# Ethernet_Adapter.net
KiCad netlist of a schematic drawn in Altium Designer
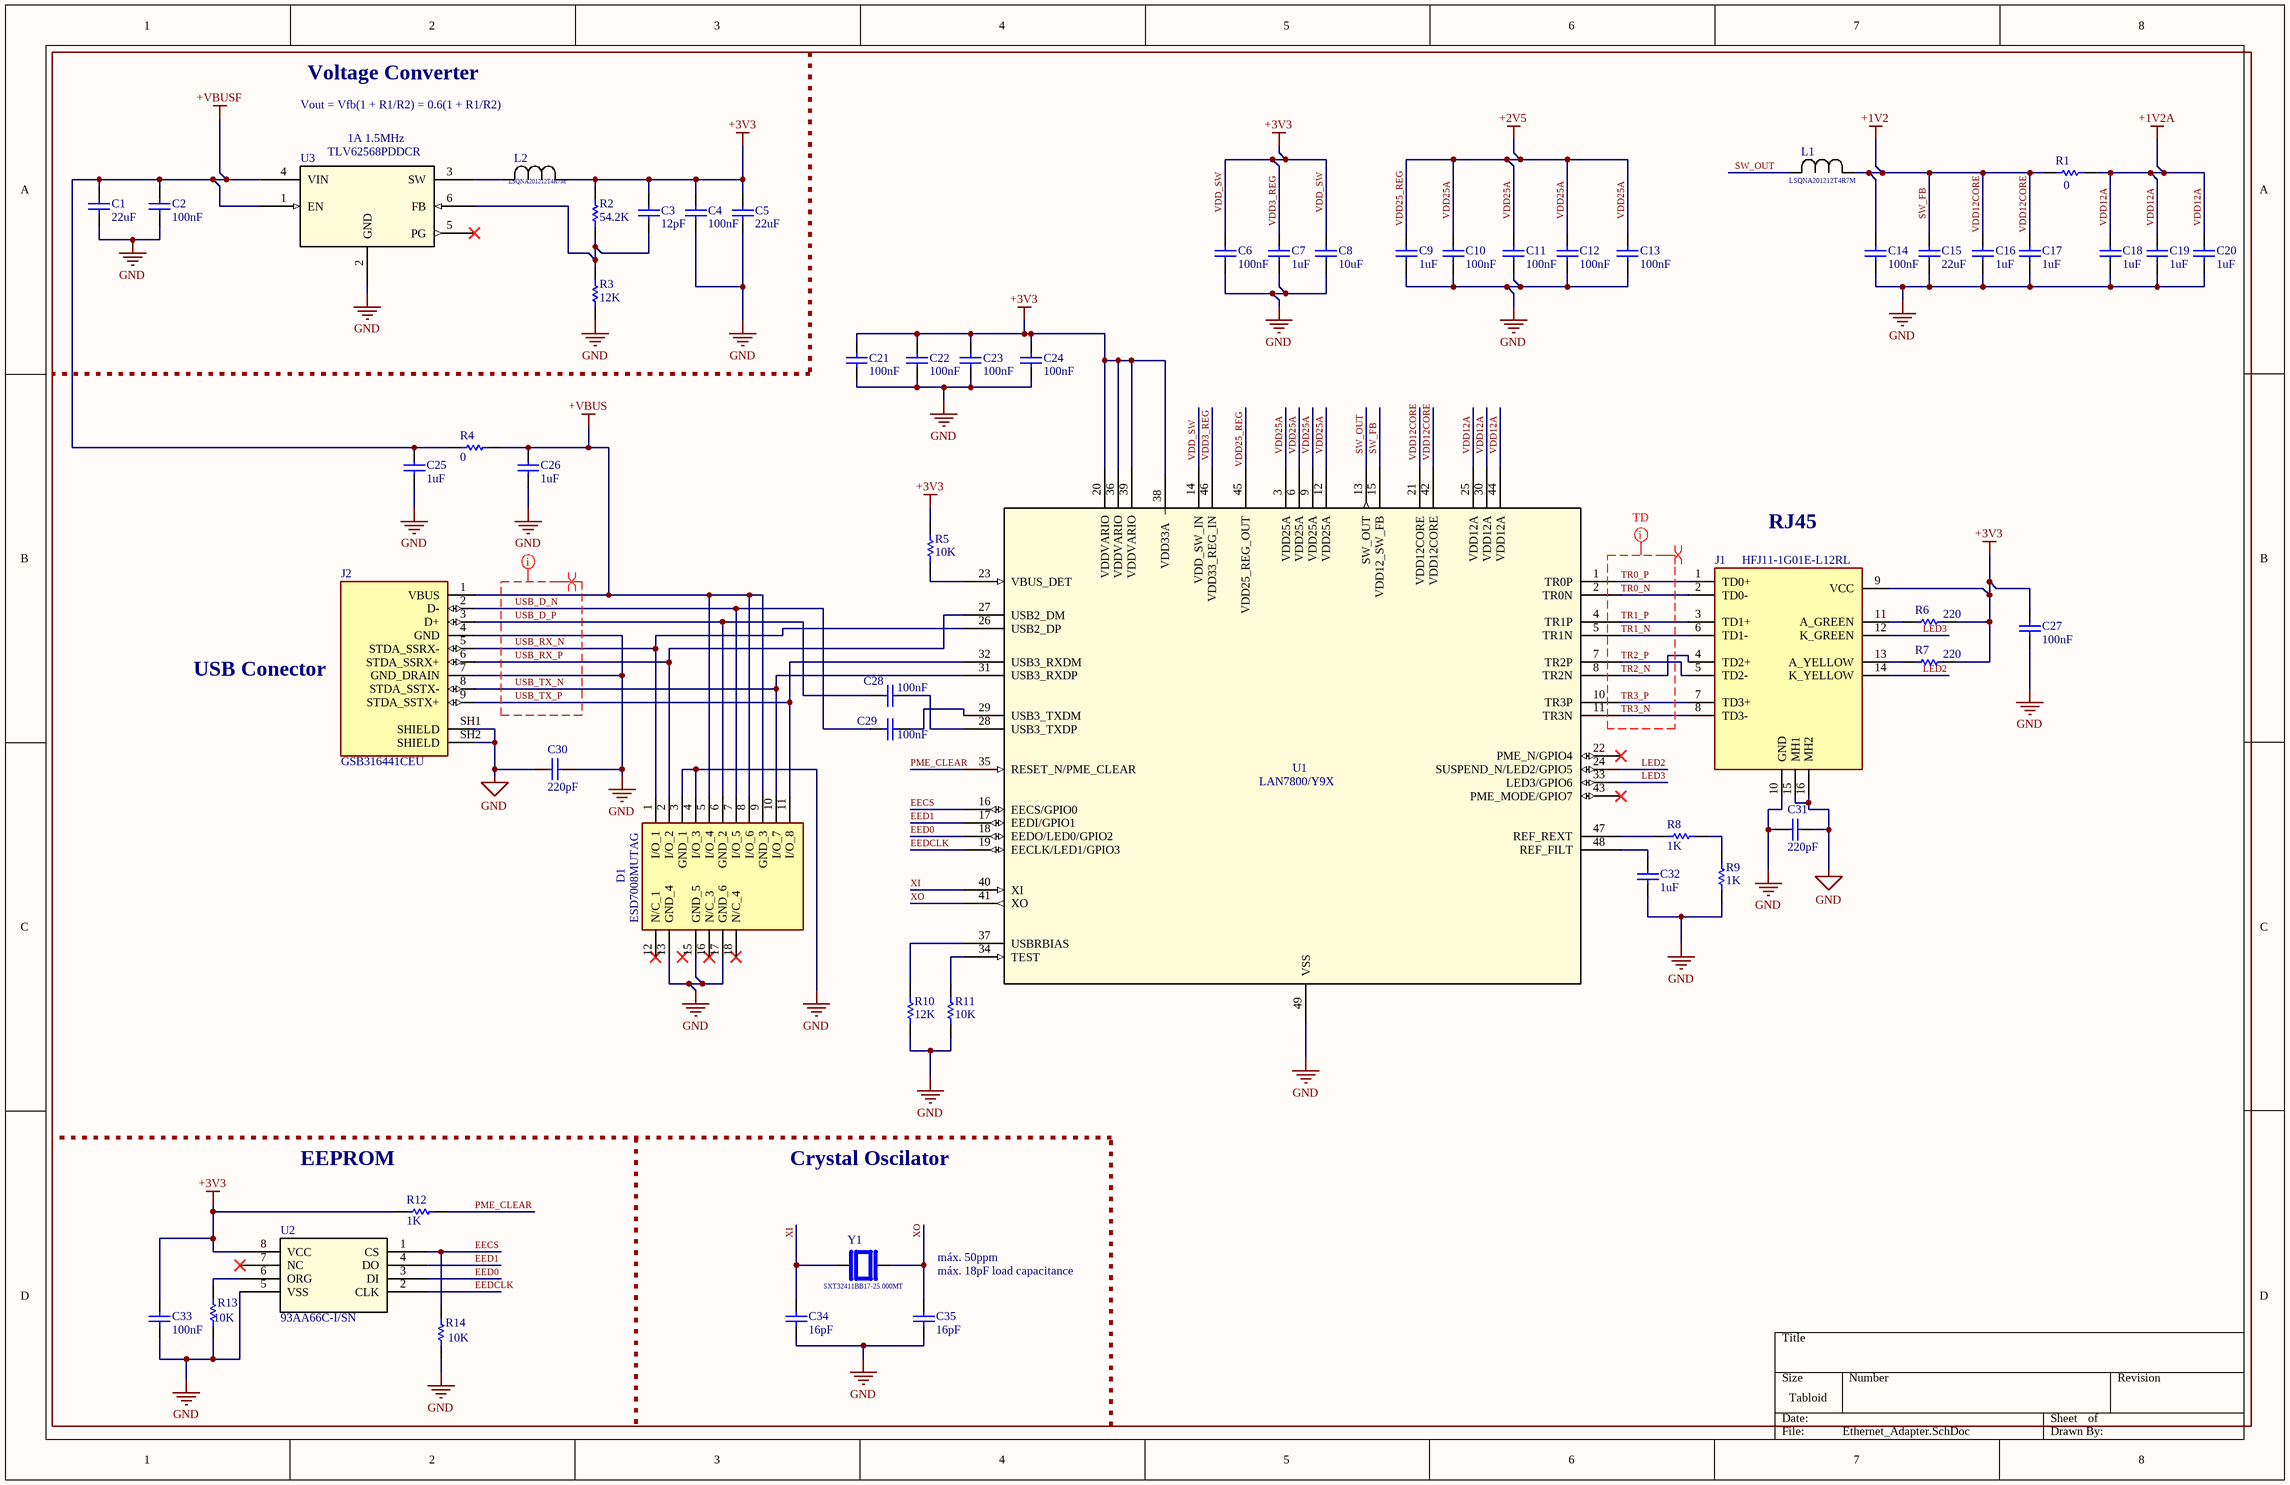
[diagram p0: Ethernet_Adapter.SchDoc]

(export (version "E")
  (design (tool "Eeschema 10.0.6"))
  (components
    (comp (ref "C1")
      (value "22uF")
      (footprint "Capacitor 0603")
      (description "Capacitor Ceramico SMD 0603")
      (libsource (lib "Mi Libreria") (part "Capacitor 0603"))
    )
    (comp (ref "C2")
      (value "100nF")
      (footprint "Capacitor 0402")
      (description "Capacitor Ceramico SMD 0402")
      (libsource (lib "Mi Libreria") (part "Capacitor 0402"))
    )
    (comp (ref "C3")
      (value "12pF")
      (footprint "Capacitor 0402")
      (description "Capacitor Ceramico SMD 0402")
      (libsource (lib "Mi Libreria") (part "Capacitor 0402"))
    )
    (comp (ref "C4")
      (value "100nF")
      (footprint "Capacitor 0402")
      (description "Capacitor Ceramico SMD 0402")
      (libsource (lib "Mi Libreria") (part "Capacitor 0402"))
    )
    (comp (ref "C5")
      (value "22uF")
      (footprint "Capacitor 0603")
      (description "Capacitor Ceramico SMD 0603")
      (libsource (lib "Mi Libreria") (part "Capacitor 0603"))
    )
    (comp (ref "C6")
      (value "100nF")
      (footprint "Capacitor 0402")
      (description "Capacitor Ceramico SMD 0402")
      (libsource (lib "Mi Libreria") (part "Capacitor 0402"))
    )
    (comp (ref "C7")
      (value "1uF")
      (footprint "Capacitor 0402")
      (description "Capacitor Ceramico SMD 0402")
      (libsource (lib "Mi Libreria") (part "Capacitor 0402"))
    )
    (comp (ref "C8")
      (value "10uF")
      (footprint "Capacitor 0402")
      (description "Capacitor Ceramico SMD 0402")
      (libsource (lib "Mi Libreria") (part "Capacitor 0402"))
    )
    (comp (ref "C9")
      (value "1uF")
      (footprint "Capacitor 0402")
      (description "Capacitor Ceramico SMD 0402")
      (libsource (lib "Mi Libreria") (part "Capacitor 0402"))
    )
    (comp (ref "C10")
      (value "100nF")
      (footprint "Capacitor 0402")
      (description "Capacitor Ceramico SMD 0402")
      (libsource (lib "Mi Libreria") (part "Capacitor 0402"))
    )
    (comp (ref "C11")
      (value "100nF")
      (footprint "Capacitor 0402")
      (description "Capacitor Ceramico SMD 0402")
      (libsource (lib "Mi Libreria") (part "Capacitor 0402"))
    )
    (comp (ref "C12")
      (value "100nF")
      (footprint "Capacitor 0402")
      (description "Capacitor Ceramico SMD 0402")
      (libsource (lib "Mi Libreria") (part "Capacitor 0402"))
    )
    (comp (ref "C13")
      (value "100nF")
      (footprint "Capacitor 0402")
      (description "Capacitor Ceramico SMD 0402")
      (libsource (lib "Mi Libreria") (part "Capacitor 0402"))
    )
    (comp (ref "C14")
      (value "100nF")
      (footprint "Capacitor 0402")
      (description "Capacitor Ceramico SMD 0402")
      (libsource (lib "Mi Libreria") (part "Capacitor 0402"))
    )
    (comp (ref "C15")
      (value "22uF")
      (footprint "Capacitor 0402")
      (description "Capacitor Ceramico SMD 0402")
      (libsource (lib "Mi Libreria") (part "Capacitor 0402"))
    )
    (comp (ref "C16")
      (value "1uF")
      (footprint "Capacitor 0402")
      (description "Capacitor Ceramico SMD 0402")
      (libsource (lib "Mi Libreria") (part "Capacitor 0402"))
    )
    (comp (ref "C17")
      (value "1uF")
      (footprint "Capacitor 0402")
      (description "Capacitor Ceramico SMD 0402")
      (libsource (lib "Mi Libreria") (part "Capacitor 0402"))
    )
    (comp (ref "C18")
      (value "1uF")
      (footprint "Capacitor 0402")
      (description "Capacitor Ceramico SMD 0402")
      (libsource (lib "Mi Libreria") (part "Capacitor 0402"))
    )
    (comp (ref "C19")
      (value "1uF")
      (footprint "Capacitor 0402")
      (description "Capacitor Ceramico SMD 0402")
      (libsource (lib "Mi Libreria") (part "Capacitor 0402"))
    )
    (comp (ref "C20")
      (value "1uF")
      (footprint "Capacitor 0402")
      (description "Capacitor Ceramico SMD 0402")
      (libsource (lib "Mi Libreria") (part "Capacitor 0402"))
    )
    (comp (ref "C21")
      (value "100nF")
      (footprint "Capacitor 0402")
      (description "Capacitor Ceramico SMD 0402")
      (libsource (lib "Mi Libreria") (part "Capacitor 0402"))
    )
    (comp (ref "C22")
      (value "100nF")
      (footprint "Capacitor 0402")
      (description "Capacitor Ceramico SMD 0402")
      (libsource (lib "Mi Libreria") (part "Capacitor 0402"))
    )
    (comp (ref "C23")
      (value "100nF")
      (footprint "Capacitor 0402")
      (description "Capacitor Ceramico SMD 0402")
      (libsource (lib "Mi Libreria") (part "Capacitor 0402"))
    )
    (comp (ref "C24")
      (value "100nF")
      (footprint "Capacitor 0402")
      (description "Capacitor Ceramico SMD 0402")
      (libsource (lib "Mi Libreria") (part "Capacitor 0402"))
    )
    (comp (ref "C25")
      (value "1uF")
      (footprint "Capacitor 0402")
      (description "Capacitor Ceramico SMD 0402")
      (libsource (lib "Mi Libreria") (part "Capacitor 0402"))
    )
    (comp (ref "C26")
      (value "1uF")
      (footprint "Capacitor 0402")
      (description "Capacitor Ceramico SMD 0402")
      (libsource (lib "Mi Libreria") (part "Capacitor 0402"))
    )
    (comp (ref "C27")
      (value "100nF")
      (footprint "Capacitor 0402")
      (description "Capacitor Ceramico SMD 0402")
      (libsource (lib "Mi Libreria") (part "Capacitor 0402"))
    )
    (comp (ref "C28")
      (value "100nF")
      (footprint "Capacitor 0402")
      (description "Capacitor Ceramico SMD 0402")
      (libsource (lib "Mi Libreria") (part "Capacitor 0402"))
    )
    (comp (ref "C29")
      (value "100nF")
      (footprint "Capacitor 0402")
      (description "Capacitor Ceramico SMD 0402")
      (libsource (lib "Mi Libreria") (part "Capacitor 0402"))
    )
    (comp (ref "C30")
      (value "220pF")
      (footprint "Capacitor 0402")
      (description "Capacitor Ceramico SMD 0402")
      (libsource (lib "Mi Libreria") (part "Capacitor 0402"))
    )
    (comp (ref "C31")
      (value "220pF")
      (footprint "Capacitor 0402")
      (description "Capacitor Ceramico SMD 0402")
      (libsource (lib "Mi Libreria") (part "Capacitor 0402"))
    )
    (comp (ref "C32")
      (value "1uF")
      (footprint "Capacitor 0402")
      (description "Capacitor Ceramico SMD 0402")
      (libsource (lib "Mi Libreria") (part "Capacitor 0402"))
    )
    (comp (ref "C33")
      (value "100nF")
      (footprint "Capacitor 0402")
      (description "Capacitor Ceramico SMD 0402")
      (libsource (lib "Mi Libreria") (part "Capacitor 0402"))
    )
    (comp (ref "C34")
      (value "16pF")
      (footprint "Capacitor 0402")
      (description "Capacitor Ceramico SMD 0402")
      (libsource (lib "Mi Libreria") (part "Capacitor 0402"))
    )
    (comp (ref "C35")
      (value "16pF")
      (footprint "Capacitor 0402")
      (description "Capacitor Ceramico SMD 0402")
      (libsource (lib "Mi Libreria") (part "Capacitor 0402"))
    )
    (comp (ref "D1")
      (value "ESD7008MUTAG")
      (footprint "ESD7008MUTAG")
      (description "10V Clamp Ipp Tvs Diode Surface Mount 18-UDFN (5.5x1.5)")
      (fields (field (name "MOUSER PART NUMBER") "863-ESD7008MUTAG"))
      (libsource (lib "ESD7008MUTAG") (part "ESD7008MUTAG"))
    )
    (comp (ref "J1")
      (value "HFJ11-1G01E-L12RL")
      (footprint "HFJ111G01EL12RL")
      (fields (field (name "MOUSER PART NUMBER") "493-HFJ111G01EL12RL"))
      (libsource (lib "HFJ11-1G01E-L12RL") (part "HFJ11-1G01E-L12RL"))
    )
    (comp (ref "J2")
      (value "GSB316441CEU")
      (footprint "AMPHENOL_GSB316441CEU")
      (fields (field (name "MF") "Amphenol"))
      (libsource (lib "GSB316441CEU") (part "GSB316441CEU"))
    )
    (comp (ref "L1")
      (value "LSQNA201212T4R7M")
      (footprint "IND_LSQN_A201212_TAY")
      (fields (field (name "COPYRIGHT") "Copyright (C) 2025 Ultra Librarian. All rights reserved."))
      (libsource (lib "LSQNA201212T4R7M") (part "LSQNA201212T4R7M"))
    )
    (comp (ref "L2")
      (value "LSQNA201212T4R7M")
      (footprint "IND_LSQN_A201212_TAY")
      (fields (field (name "COPYRIGHT") "Copyright (C) 2025 Ultra Librarian. All rights reserved."))
      (libsource (lib "LSQNA201212T4R7M") (part "LSQNA201212T4R7M"))
    )
    (comp (ref "R1")
      (value "0")
      (footprint "Resistencia 0402")
      (description "Resistencia SMD 0402")
      (libsource (lib "Mi Libreria") (part "Resistencia SMD 0402"))
    )
    (comp (ref "R2")
      (value "54.2K")
      (footprint "Resistencia 0402")
      (description "Resistencia SMD 0402")
      (libsource (lib "Mi Libreria") (part "Resistencia SMD 0402"))
    )
    (comp (ref "R3")
      (value "12K")
      (footprint "Resistencia 0402")
      (description "Resistencia SMD 0402")
      (libsource (lib "Mi Libreria") (part "Resistencia SMD 0402"))
    )
    (comp (ref "R4")
      (value "0")
      (footprint "Resistencia 0402")
      (description "Resistencia SMD 0402")
      (libsource (lib "Mi Libreria") (part "Resistencia SMD 0402"))
    )
    (comp (ref "R5")
      (value "10K")
      (footprint "Resistencia 0402")
      (description "Resistencia SMD 0402")
      (libsource (lib "Mi Libreria") (part "Resistencia SMD 0402"))
    )
    (comp (ref "R6")
      (value "220")
      (footprint "Resistencia 0402")
      (description "Resistencia SMD 0402")
      (libsource (lib "Mi Libreria") (part "Resistencia SMD 0402"))
    )
    (comp (ref "R7")
      (value "220")
      (footprint "Resistencia 0402")
      (description "Resistencia SMD 0402")
      (libsource (lib "Mi Libreria") (part "Resistencia SMD 0402"))
    )
    (comp (ref "R8")
      (value "1K")
      (footprint "Resistencia 0402")
      (description "Resistencia SMD 0402")
      (libsource (lib "Mi Libreria") (part "Resistencia SMD 0402"))
    )
    (comp (ref "R9")
      (value "1K")
      (footprint "Resistencia 0402")
      (description "Resistencia SMD 0402")
      (libsource (lib "Mi Libreria") (part "Resistencia SMD 0402"))
    )
    (comp (ref "R10")
      (value "12K")
      (footprint "Resistencia 0402")
      (description "Resistencia SMD 0402")
      (libsource (lib "Mi Libreria") (part "Resistencia SMD 0402"))
    )
    (comp (ref "R11")
      (value "10K")
      (footprint "Resistencia 0402")
      (description "Resistencia SMD 0402")
      (libsource (lib "Mi Libreria") (part "Resistencia SMD 0402"))
    )
    (comp (ref "R12")
      (value "1K")
      (footprint "Resistencia 0402")
      (description "Resistencia SMD 0402")
      (libsource (lib "Mi Libreria") (part "Resistencia SMD 0402"))
    )
    (comp (ref "R13")
      (value "10K")
      (footprint "Resistencia 0402")
      (description "Resistencia SMD 0402")
      (libsource (lib "Mi Libreria") (part "Resistencia SMD 0402"))
    )
    (comp (ref "R14")
      (value "10K")
      (footprint "Resistencia 0402")
      (description "Resistencia SMD 0402")
      (libsource (lib "Mi Libreria") (part "Resistencia SMD 0402"))
    )
    (comp (ref "U1")
      (value "LAN7800/Y9X")
      (footprint "SQFN48_7X7_Y9X_MCH")
      (description "Description")
      (fields (field (name "COPYRIGHT") "Copyright (C) 2025 Ultra Librarian. All rights reserved."))
      (libsource (lib "LAN7800Y9X") (part "LAN7800Y9X"))
    )
    (comp (ref "U2")
      (value "93AA66C-I/SN")
      (footprint "SOIC8-N_MC_MCH")
      (description "IC EEPROM 4KBIT MICROWIRE 8SOIC")
      (fields (field (name "COPYRIGHT") "Copyright (C) 2026 Ultra Librarian. All rights reserved."))
      (libsource (lib "93AA66C-ISN") (part "93AA66C-ISN"))
    )
    (comp (ref "U3")
      (value "TLV62568PDDCR")
      (footprint "DDC0006A_TEX")
      (fields (field (name "COPYRIGHT") "Copyright (C) 2026 Ultra Librarian. All rights reserved."))
      (libsource (lib "TLV62568PDDCR") (part "TLV62568PDDCR"))
    )
    (comp (ref "Y1")
      (value "SXT32411BB17-25.000MT")
      (footprint "XTAL_SXT32411BB17-25.000MT")
      (fields (field (name "MF") "{'manufacturer': u'Suntsu Electronics, Inc'}"))
      (libsource (lib "SXT32411BB17-25.000MT") (part "SXT32411BB17-25.000MT"))
    )
  )
  (nets
    (net (code "1") (name "+1V2") (class "Default")
      (node (ref "C14") (pin "2") (pinfunction "2_2") (pintype "passive"))
      (node (ref "C15") (pin "2") (pinfunction "2_2") (pintype "passive"))
      (node (ref "C16") (pin "2") (pinfunction "2_2") (pintype "passive"))
      (node (ref "C17") (pin "2") (pinfunction "2_2") (pintype "passive"))
      (node (ref "L1") (pin "1") (pinfunction "1_1") (pintype "passive"))
      (node (ref "R1") (pin "1") (pinfunction "A_1") (pintype "passive"))
      (node (ref "U1") (pin "15") (pinfunction "VDD12_SW_FB_15") (pintype "power_in"))
      (node (ref "U1") (pin "21") (pinfunction "VDD12CORE_21") (pintype "power_in"))
      (node (ref "U1") (pin "42") (pinfunction "VDD12CORE_42") (pintype "power_in"))
    )
    (net (code "2") (name "+1V2A") (class "Default")
      (node (ref "C18") (pin "2") (pinfunction "2_2") (pintype "passive"))
      (node (ref "C19") (pin "2") (pinfunction "2_2") (pintype "passive"))
      (node (ref "C20") (pin "2") (pinfunction "2_2") (pintype "passive"))
      (node (ref "R1") (pin "2") (pinfunction "B_2") (pintype "passive"))
      (node (ref "U1") (pin "25") (pinfunction "VDD12A_25") (pintype "power_in"))
      (node (ref "U1") (pin "30") (pinfunction "VDD12A_30") (pintype "power_in"))
      (node (ref "U1") (pin "44") (pinfunction "VDD12A_44") (pintype "power_in"))
    )
    (net (code "3") (name "+2V5") (class "Default")
      (node (ref "C10") (pin "2") (pinfunction "2_2") (pintype "passive"))
      (node (ref "C11") (pin "2") (pinfunction "2_2") (pintype "passive"))
      (node (ref "C12") (pin "2") (pinfunction "2_2") (pintype "passive"))
      (node (ref "C13") (pin "2") (pinfunction "2_2") (pintype "passive"))
      (node (ref "C9") (pin "2") (pinfunction "2_2") (pintype "passive"))
      (node (ref "U1") (pin "12") (pinfunction "VDD25A_12") (pintype "power_in"))
      (node (ref "U1") (pin "3") (pinfunction "VDD25A_3") (pintype "power_in"))
      (node (ref "U1") (pin "45") (pinfunction "VDD25_REG_OUT_45") (pintype "power_in"))
      (node (ref "U1") (pin "6") (pinfunction "VDD25A_6") (pintype "power_in"))
      (node (ref "U1") (pin "9") (pinfunction "VDD25A_9") (pintype "power_in"))
    )
    (net (code "4") (name "+3V3") (class "Default")
      (node (ref "C21") (pin "2") (pinfunction "2_2") (pintype "passive"))
      (node (ref "C22") (pin "2") (pinfunction "2_2") (pintype "passive"))
      (node (ref "C23") (pin "2") (pinfunction "2_2") (pintype "passive"))
      (node (ref "C24") (pin "2") (pinfunction "2_2") (pintype "passive"))
      (node (ref "C27") (pin "2") (pinfunction "2_2") (pintype "passive"))
      (node (ref "C3") (pin "2") (pinfunction "2_2") (pintype "passive"))
      (node (ref "C33") (pin "2") (pinfunction "2_2") (pintype "passive"))
      (node (ref "C4") (pin "2") (pinfunction "2_2") (pintype "passive"))
      (node (ref "C5") (pin "2") (pinfunction "2_2") (pintype "passive"))
      (node (ref "C6") (pin "2") (pinfunction "2_2") (pintype "passive"))
      (node (ref "C7") (pin "2") (pinfunction "2_2") (pintype "passive"))
      (node (ref "C8") (pin "2") (pinfunction "2_2") (pintype "passive"))
      (node (ref "J1") (pin "9") (pinfunction "VCC_9") (pintype "passive"))
      (node (ref "L2") (pin "1") (pinfunction "1_1") (pintype "passive"))
      (node (ref "R12") (pin "1") (pinfunction "A_1") (pintype "passive"))
      (node (ref "R2") (pin "2") (pinfunction "B_2") (pintype "passive"))
      (node (ref "R5") (pin "2") (pinfunction "B_2") (pintype "passive"))
      (node (ref "R6") (pin "2") (pinfunction "B_2") (pintype "passive"))
      (node (ref "R7") (pin "2") (pinfunction "B_2") (pintype "passive"))
      (node (ref "U1") (pin "14") (pinfunction "VDD_SW_IN_14") (pintype "power_in"))
      (node (ref "U1") (pin "20") (pinfunction "VDDVARIO_20") (pintype "power_in"))
      (node (ref "U1") (pin "36") (pinfunction "VDDVARIO_36") (pintype "power_in"))
      (node (ref "U1") (pin "38") (pinfunction "VDD33A_38") (pintype "power_in"))
      (node (ref "U1") (pin "39") (pinfunction "VDDVARIO_39") (pintype "power_in"))
      (node (ref "U1") (pin "46") (pinfunction "VDD33_REG_IN_46") (pintype "power_in"))
      (node (ref "U2") (pin "8") (pinfunction "VCC_8") (pintype "passive"))
    )
    (net (code "5") (name "+VBUS") (class "Default")
      (node (ref "C26") (pin "2") (pinfunction "2_2") (pintype "passive"))
      (node (ref "D1") (pin "5") (pinfunction "I/O_4_5") (pintype "passive"))
      (node (ref "D1") (pin "8") (pinfunction "I/O_6_8") (pintype "passive"))
      (node (ref "D1") (pin "9") (pinfunction "GND_3_9") (pintype "passive"))
      (node (ref "J2") (pin "1") (pinfunction "VBUS_1") (pintype "power_in"))
      (node (ref "R4") (pin "2") (pinfunction "B_2") (pintype "passive"))
    )
    (net (code "6") (name "+VBUSF") (class "Default")
      (node (ref "C1") (pin "2") (pinfunction "2_2") (pintype "passive"))
      (node (ref "C2") (pin "2") (pinfunction "2_2") (pintype "passive"))
      (node (ref "C25") (pin "2") (pinfunction "2_2") (pintype "passive"))
      (node (ref "R4") (pin "1") (pinfunction "A_1") (pintype "passive"))
      (node (ref "U3") (pin "1") (pinfunction "EN_1") (pintype "input"))
      (node (ref "U3") (pin "4") (pinfunction "VIN_4") (pintype "power_in"))
    )
    (net (code "7") (name "/EECS") (class "Default")
      (node (ref "R14") (pin "2") (pinfunction "B_2") (pintype "passive"))
      (node (ref "U1") (pin "16") (pinfunction "EECS/GPIO0_16") (pintype "bidirectional"))
      (node (ref "U2") (pin "1") (pinfunction "CS_1") (pintype "passive"))
    )
    (net (code "8") (name "/EED0") (class "Default")
      (node (ref "U1") (pin "18") (pinfunction "EEDO/LED0/GPIO2_18") (pintype "bidirectional"))
      (node (ref "U2") (pin "3") (pinfunction "DI_3") (pintype "passive"))
    )
    (net (code "9") (name "/EED1") (class "Default")
      (node (ref "U1") (pin "17") (pinfunction "EEDI/GPIO1_17") (pintype "bidirectional"))
      (node (ref "U2") (pin "4") (pinfunction "DO_4") (pintype "passive"))
    )
    (net (code "10") (name "/EEDCLK") (class "Default")
      (node (ref "U1") (pin "19") (pinfunction "EECLK/LED1/GPIO3_19") (pintype "bidirectional"))
      (node (ref "U2") (pin "2") (pinfunction "CLK_2") (pintype "passive"))
    )
    (net (code "11") (name "/LED2") (class "Default")
      (node (ref "J1") (pin "14") (pinfunction "K_YELLOW_14") (pintype "passive"))
      (node (ref "U1") (pin "24") (pinfunction "SUSPEND_N/LED2/GPIO5_24") (pintype "bidirectional"))
    )
    (net (code "12") (name "/LED3") (class "Default")
      (node (ref "J1") (pin "12") (pinfunction "K_GREEN_12") (pintype "passive"))
      (node (ref "U1") (pin "33") (pinfunction "LED3/GPIO6_33") (pintype "bidirectional"))
    )
    (net (code "13") (name "/PME_CLEAR") (class "Default")
      (node (ref "R12") (pin "2") (pinfunction "B_2") (pintype "passive"))
      (node (ref "U1") (pin "35") (pinfunction "RESET_N/PME_CLEAR_35") (pintype "input"))
    )
    (net (code "14") (name "/SW_OUT") (class "Default")
      (node (ref "L1") (pin "2") (pinfunction "2_2") (pintype "passive"))
      (node (ref "U1") (pin "13") (pinfunction "SW_OUT_13") (pintype "output"))
    )
    (net (code "15") (name "/TR0_N") (class "Default")
      (node (ref "J1") (pin "2") (pinfunction "TD0-_2") (pintype "passive"))
      (node (ref "U1") (pin "2") (pinfunction "TR0N_2") (pintype "passive"))
    )
    (net (code "16") (name "/TR0_P") (class "Default")
      (node (ref "J1") (pin "1") (pinfunction "TD0+_1") (pintype "passive"))
      (node (ref "U1") (pin "1") (pinfunction "TR0P_1") (pintype "passive"))
    )
    (net (code "17") (name "/TR1_N") (class "Default")
      (node (ref "J1") (pin "6") (pinfunction "TD1-_6") (pintype "passive"))
      (node (ref "U1") (pin "5") (pinfunction "TR1N_5") (pintype "passive"))
    )
    (net (code "18") (name "/TR1_P") (class "Default")
      (node (ref "J1") (pin "3") (pinfunction "TD1+_3") (pintype "passive"))
      (node (ref "U1") (pin "4") (pinfunction "TR1P_4") (pintype "passive"))
    )
    (net (code "19") (name "/TR2_N") (class "Default")
      (node (ref "J1") (pin "4") (pinfunction "TD2+_4") (pintype "passive"))
      (node (ref "U1") (pin "8") (pinfunction "TR2N_8") (pintype "passive"))
    )
    (net (code "20") (name "/TR2_P") (class "Default")
      (node (ref "J1") (pin "5") (pinfunction "TD2-_5") (pintype "passive"))
      (node (ref "U1") (pin "7") (pinfunction "TR2P_7") (pintype "passive"))
    )
    (net (code "21") (name "/TR3_N") (class "Default")
      (node (ref "J1") (pin "8") (pinfunction "TD3-_8") (pintype "passive"))
      (node (ref "U1") (pin "11") (pinfunction "TR3N_11") (pintype "passive"))
    )
    (net (code "22") (name "/TR3_P") (class "Default")
      (node (ref "J1") (pin "7") (pinfunction "TD3+_7") (pintype "passive"))
      (node (ref "U1") (pin "10") (pinfunction "TR3P_10") (pintype "passive"))
    )
    (net (code "23") (name "/USB_D_N") (class "Default")
      (node (ref "C29") (pin "2") (pinfunction "2_2") (pintype "passive"))
      (node (ref "D1") (pin "7") (pinfunction "I/O_5_7") (pintype "passive"))
      (node (ref "J2") (pin "2") (pinfunction "D-_2") (pintype "bidirectional"))
    )
    (net (code "24") (name "/USB_D_P") (class "Default")
      (node (ref "C28") (pin "2") (pinfunction "2_2") (pintype "passive"))
      (node (ref "D1") (pin "6") (pinfunction "GND_2_6") (pintype "passive"))
      (node (ref "J2") (pin "3") (pinfunction "D+_3") (pintype "bidirectional"))
    )
    (net (code "25") (name "/USB_RX_N") (class "Default")
      (node (ref "D1") (pin "1") (pinfunction "I/O_1_1") (pintype "passive"))
      (node (ref "J2") (pin "5") (pinfunction "STDA_SSRX-_5") (pintype "bidirectional"))
      (node (ref "U1") (pin "26") (pinfunction "USB2_DP_26") (pintype "passive"))
    )
    (net (code "26") (name "/USB_RX_P") (class "Default")
      (node (ref "D1") (pin "2") (pinfunction "I/O_2_2") (pintype "passive"))
      (node (ref "J2") (pin "6") (pinfunction "STDA_SSRX+_6") (pintype "bidirectional"))
      (node (ref "U1") (pin "27") (pinfunction "USB2_DM_27") (pintype "passive"))
    )
    (net (code "27") (name "/USB_TX_N") (class "Default")
      (node (ref "D1") (pin "10") (pinfunction "I/O_7_10") (pintype "passive"))
      (node (ref "J2") (pin "8") (pinfunction "STDA_SSTX-_8") (pintype "bidirectional"))
      (node (ref "U1") (pin "31") (pinfunction "USB3_RXDP_31") (pintype "passive"))
    )
    (net (code "28") (name "/USB_TX_P") (class "Default")
      (node (ref "D1") (pin "11") (pinfunction "I/O_8_11") (pintype "passive"))
      (node (ref "J2") (pin "9") (pinfunction "STDA_SSTX+_9") (pintype "bidirectional"))
      (node (ref "U1") (pin "32") (pinfunction "USB3_RXDM_32") (pintype "passive"))
    )
    (net (code "29") (name "/XI") (class "Default")
      (node (ref "C34") (pin "2") (pinfunction "2_2") (pintype "passive"))
      (node (ref "U1") (pin "40") (pinfunction "XI_40") (pintype "input"))
      (node (ref "Y1") (pin "3") (pinfunction "3_3") (pintype "passive"))
    )
    (net (code "30") (name "/XO") (class "Default")
      (node (ref "C35") (pin "2") (pinfunction "2_2") (pintype "passive"))
      (node (ref "U1") (pin "41") (pinfunction "XO_41") (pintype "output"))
      (node (ref "Y1") (pin "1") (pinfunction "1_1") (pintype "passive"))
    )
    (net (code "31") (name "GND") (class "Default")
      (node (ref "C1") (pin "1") (pinfunction "1_1") (pintype "passive"))
      (node (ref "C10") (pin "1") (pinfunction "1_1") (pintype "passive"))
      (node (ref "C11") (pin "1") (pinfunction "1_1") (pintype "passive"))
      (node (ref "C12") (pin "1") (pinfunction "1_1") (pintype "passive"))
      (node (ref "C13") (pin "1") (pinfunction "1_1") (pintype "passive"))
      (node (ref "C14") (pin "1") (pinfunction "1_1") (pintype "passive"))
      (node (ref "C15") (pin "1") (pinfunction "1_1") (pintype "passive"))
      (node (ref "C16") (pin "1") (pinfunction "1_1") (pintype "passive"))
      (node (ref "C17") (pin "1") (pinfunction "1_1") (pintype "passive"))
      (node (ref "C18") (pin "1") (pinfunction "1_1") (pintype "passive"))
      (node (ref "C19") (pin "1") (pinfunction "1_1") (pintype "passive"))
      (node (ref "C2") (pin "1") (pinfunction "1_1") (pintype "passive"))
      (node (ref "C20") (pin "1") (pinfunction "1_1") (pintype "passive"))
      (node (ref "C21") (pin "1") (pinfunction "1_1") (pintype "passive"))
      (node (ref "C22") (pin "1") (pinfunction "1_1") (pintype "passive"))
      (node (ref "C23") (pin "1") (pinfunction "1_1") (pintype "passive"))
      (node (ref "C24") (pin "1") (pinfunction "1_1") (pintype "passive"))
      (node (ref "C25") (pin "1") (pinfunction "1_1") (pintype "passive"))
      (node (ref "C26") (pin "1") (pinfunction "1_1") (pintype "passive"))
      (node (ref "C27") (pin "1") (pinfunction "1_1") (pintype "passive"))
      (node (ref "C30") (pin "1") (pinfunction "1_1") (pintype "passive"))
      (node (ref "C30") (pin "2") (pinfunction "2_2") (pintype "passive"))
      (node (ref "C31") (pin "1") (pinfunction "1_1") (pintype "passive"))
      (node (ref "C31") (pin "2") (pinfunction "2_2") (pintype "passive"))
      (node (ref "C32") (pin "1") (pinfunction "1_1") (pintype "passive"))
      (node (ref "C33") (pin "1") (pinfunction "1_1") (pintype "passive"))
      (node (ref "C34") (pin "1") (pinfunction "1_1") (pintype "passive"))
      (node (ref "C35") (pin "1") (pinfunction "1_1") (pintype "passive"))
      (node (ref "C4") (pin "1") (pinfunction "1_1") (pintype "passive"))
      (node (ref "C5") (pin "1") (pinfunction "1_1") (pintype "passive"))
      (node (ref "C6") (pin "1") (pinfunction "1_1") (pintype "passive"))
      (node (ref "C7") (pin "1") (pinfunction "1_1") (pintype "passive"))
      (node (ref "C8") (pin "1") (pinfunction "1_1") (pintype "passive"))
      (node (ref "C9") (pin "1") (pinfunction "1_1") (pintype "passive"))
      (node (ref "D1") (pin "13") (pinfunction "GND_4_13") (pintype "passive"))
      (node (ref "D1") (pin "15") (pinfunction "GND_5_15") (pintype "passive"))
      (node (ref "D1") (pin "17") (pinfunction "GND_6_17") (pintype "passive"))
      (node (ref "D1") (pin "3") (pinfunction "GND_1_3") (pintype "passive"))
      (node (ref "D1") (pin "4") (pinfunction "I/O_3_4") (pintype "passive"))
      (node (ref "J1") (pin "10") (pinfunction "GND_10") (pintype "passive"))
      (node (ref "J1") (pin "15") (pinfunction "MH1_15") (pintype "passive"))
      (node (ref "J1") (pin "16") (pinfunction "MH2_16") (pintype "passive"))
      (node (ref "J2") (pin "4") (pinfunction "GND_4") (pintype "power_in"))
      (node (ref "J2") (pin "7") (pinfunction "GND_DRAIN_7") (pintype "power_in"))
      (node (ref "J2") (pin "SH1") (pinfunction "SHIELD_SH1") (pintype "passive"))
      (node (ref "J2") (pin "SH2") (pinfunction "SHIELD_SH2") (pintype "passive"))
      (node (ref "R10") (pin "1") (pinfunction "A_1") (pintype "passive"))
      (node (ref "R11") (pin "1") (pinfunction "A_1") (pintype "passive"))
      (node (ref "R13") (pin "1") (pinfunction "A_1") (pintype "passive"))
      (node (ref "R14") (pin "1") (pinfunction "A_1") (pintype "passive"))
      (node (ref "R3") (pin "1") (pinfunction "A_1") (pintype "passive"))
      (node (ref "R9") (pin "1") (pinfunction "A_1") (pintype "passive"))
      (node (ref "U1") (pin "49") (pinfunction "VSS_49") (pintype "power_in"))
      (node (ref "U2") (pin "5") (pinfunction "VSS_5") (pintype "passive"))
      (node (ref "U3") (pin "2") (pinfunction "GND_2") (pintype "power_in"))
    )
    (net (code "32") (name "Net-(J1-A_GREEN)") (class "Default")
      (node (ref "J1") (pin "11") (pinfunction "A_GREEN_11") (pintype "passive"))
      (node (ref "R6") (pin "1") (pinfunction "A_1") (pintype "passive"))
    )
    (net (code "33") (name "Net-(J1-A_YELLOW)") (class "Default")
      (node (ref "J1") (pin "13") (pinfunction "A_YELLOW_13") (pintype "passive"))
      (node (ref "R7") (pin "1") (pinfunction "A_1") (pintype "passive"))
    )
    (net (code "34") (name "Net-(R2-A)") (class "Default")
      (node (ref "C3") (pin "1") (pinfunction "1_1") (pintype "passive"))
      (node (ref "R2") (pin "1") (pinfunction "A_1") (pintype "passive"))
      (node (ref "R3") (pin "2") (pinfunction "B_2") (pintype "passive"))
      (node (ref "U3") (pin "6") (pinfunction "FB_6") (pintype "input"))
    )
    (net (code "35") (name "Net-(R5-A)") (class "Default")
      (node (ref "R5") (pin "1") (pinfunction "A_1") (pintype "passive"))
      (node (ref "U1") (pin "23") (pinfunction "VBUS_DET_23") (pintype "input"))
    )
    (net (code "36") (name "Net-(R8-A)") (class "Default")
      (node (ref "R8") (pin "1") (pinfunction "A_1") (pintype "passive"))
      (node (ref "U1") (pin "47") (pinfunction "REF_REXT_47") (pintype "passive"))
    )
    (net (code "37") (name "Net-(R8-B)") (class "Default")
      (node (ref "R8") (pin "2") (pinfunction "B_2") (pintype "passive"))
      (node (ref "R9") (pin "2") (pinfunction "B_2") (pintype "passive"))
    )
    (net (code "38") (name "Net-(R10-B)") (class "Default")
      (node (ref "R10") (pin "2") (pinfunction "B_2") (pintype "passive"))
      (node (ref "U1") (pin "37") (pinfunction "USBRBIAS_37") (pintype "passive"))
    )
    (net (code "39") (name "Net-(R11-B)") (class "Default")
      (node (ref "R11") (pin "2") (pinfunction "B_2") (pintype "passive"))
      (node (ref "U1") (pin "34") (pinfunction "TEST_34") (pintype "input"))
    )
    (net (code "40") (name "Net-(R13-B)") (class "Default")
      (node (ref "R13") (pin "2") (pinfunction "B_2") (pintype "passive"))
      (node (ref "U2") (pin "6") (pinfunction "ORG_6") (pintype "passive"))
    )
    (net (code "41") (name "Net-(U1-REF_FILT)") (class "Default")
      (node (ref "C32") (pin "2") (pinfunction "2_2") (pintype "passive"))
      (node (ref "U1") (pin "48") (pinfunction "REF_FILT_48") (pintype "passive"))
    )
    (net (code "42") (name "Net-(U1-USB3_TXDM)") (class "Default")
      (node (ref "C29") (pin "1") (pinfunction "1_1") (pintype "passive"))
      (node (ref "U1") (pin "29") (pinfunction "USB3_TXDM_29") (pintype "passive"))
    )
    (net (code "43") (name "Net-(U1-USB3_TXDP)") (class "Default")
      (node (ref "C28") (pin "1") (pinfunction "1_1") (pintype "passive"))
      (node (ref "U1") (pin "28") (pinfunction "USB3_TXDP_28") (pintype "passive"))
    )
    (net (code "44") (name "Net-(U3-SW)") (class "Default")
      (node (ref "L2") (pin "2") (pinfunction "2_2") (pintype "passive"))
      (node (ref "U3") (pin "3") (pinfunction "SW_3") (pintype "power_in"))
    )
    (net (code "45") (name "unconnected-(D1-N{slash}C_1-Pad12)") (class "Default")
      (node (ref "D1") (pin "12") (pinfunction "N/C_1_12") (pintype "passive+no_connect"))
    )
    (net (code "46") (name "unconnected-(D1-N{slash}C_3-Pad16)") (class "Default")
      (node (ref "D1") (pin "16") (pinfunction "N/C_3_16") (pintype "passive+no_connect"))
    )
    (net (code "47") (name "unconnected-(D1-N{slash}C_4-Pad18)") (class "Default")
      (node (ref "D1") (pin "18") (pinfunction "N/C_4_18") (pintype "passive+no_connect"))
    )
    (net (code "48") (name "unconnected-(U1-PME_MODE{slash}GPIO7-Pad43)") (class "Default")
      (node (ref "U1") (pin "43") (pinfunction "PME_MODE/GPIO7_43") (pintype "bidirectional+no_connect"))
    )
    (net (code "49") (name "unconnected-(U1-PME_N{slash}GPIO4-Pad22)") (class "Default")
      (node (ref "U1") (pin "22") (pinfunction "PME_N/GPIO4_22") (pintype "bidirectional+no_connect"))
    )
    (net (code "50") (name "unconnected-(U2-NC-Pad7)") (class "Default")
      (node (ref "U2") (pin "7") (pinfunction "NC_7") (pintype "passive+no_connect"))
    )
    (net (code "51") (name "unconnected-(U3-PG-Pad5)") (class "Default")
      (node (ref "U3") (pin "5") (pinfunction "PG_5") (pintype "output+no_connect"))
    )
  )
)
